# Busswitch_A.net
KiCad netlist of a schematic drawn in Altium Designer
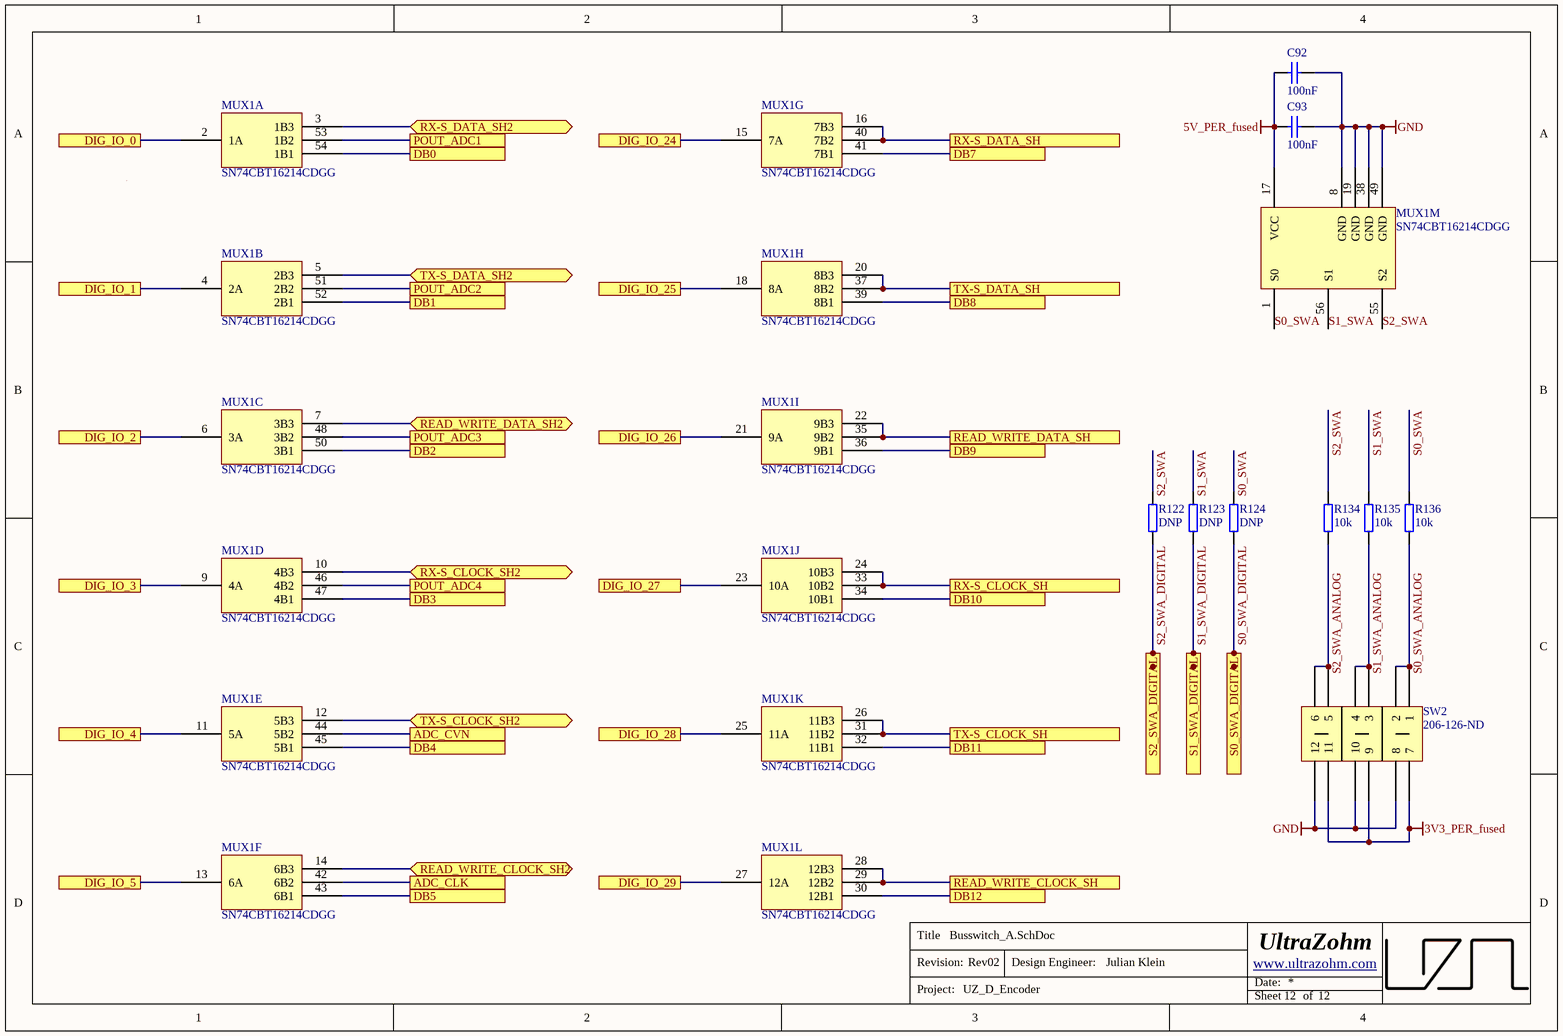
[diagram p0: Busswitch_A.SchDoc]

(export (version "E")
  (design (tool "Eeschema 10.0.6"))
  (components
    (comp (ref "C92")
      (value "100nF")
      (footprint "CAPC1608X07N")
      (fields (field (name "MF") "Würth") (field (name "MPN") "885012206071") (field (name "VOLTAGE") "25V"))
      (libsource (lib "UltraZohm_ADC") (part "Cap_0603"))
    )
    (comp (ref "C93")
      (value "100nF")
      (footprint "CAPC1608X07N")
      (fields (field (name "MF") "Würth") (field (name "MPN") "885012206071") (field (name "VOLTAGE") "25V"))
      (libsource (lib "UltraZohm_ADC") (part "Cap_0603"))
    )
    (comp (ref "MUX1")
      (value "SN74CBT16214CDGG")
      (footprint "TSSOP50P810X120-56N")
      (description "Multiplexer/Demultiplexer Bus Switch 1-Element CMOS 36-IN 56-Pin TSSOP Tube")
      (fields
        (field (name "MANUFACTURER") "Texas Instruments")
        (field (name "SUPPLIER PART NUMBER 1") "SN74CBT16214CDGG")
      )
      (libsource (lib "uz_d_encoder_lib") (part "SN74CBT16214CDGG"))
    )
    (comp (ref "R122")
      (value "DNP")
      (footprint "RESC1608X06N")
      (fields (field (name "MF") "Vishay") (field (name "MPN") "CRCW06030000Z0EAC"))
      (libsource (lib "UltraZohm_ADC") (part "R_0603"))
    )
    (comp (ref "R123")
      (value "DNP")
      (footprint "RESC1608X06N")
      (fields (field (name "MF") "Vishay") (field (name "MPN") "CRCW06030000Z0EAC"))
      (libsource (lib "UltraZohm_ADC") (part "R_0603"))
    )
    (comp (ref "R124")
      (value "DNP")
      (footprint "RESC1608X06N")
      (fields (field (name "MF") "Vishay") (field (name "MPN") "CRCW06030000Z0EAC"))
      (libsource (lib "UltraZohm_ADC") (part "R_0603"))
    )
    (comp (ref "R134")
      (value "10k")
      (footprint "RESC1608X06N")
      (fields (field (name "MF") "Vishay") (field (name "MPN") "CRCW06030000Z0EAC"))
      (libsource (lib "UltraZohm_ADC") (part "R_0603"))
    )
    (comp (ref "R135")
      (value "10k")
      (footprint "RESC1608X06N")
      (fields (field (name "MF") "Vishay") (field (name "MPN") "CRCW06030000Z0EAC"))
      (libsource (lib "UltraZohm_ADC") (part "R_0603"))
    )
    (comp (ref "R136")
      (value "10k")
      (footprint "RESC1608X06N")
      (fields (field (name "MF") "Vishay") (field (name "MPN") "CRCW06030000Z0EAC"))
      (libsource (lib "UltraZohm_ADC") (part "R_0603"))
    )
    (comp (ref "SW2")
      (value "206-126")
      (footprint "206-123")
      (description "Switch DIP OFF ON SPDT 6 Raised Slide 0.05A 24VDC PC Pins 2.54mm Thru-Hole Tube")
      (fields (field (name "MANUFACTURER") "CTS") (field (name "SUPPLIER PART NUMBER 1") "206-126-ND"))
      (libsource (lib "uz_d_encoder_lib") (part "206-126"))
    )
  )
  (nets
    (net (code "1") (name "/ADC_CLK") (class "Default")
      (node (ref "MUX1") (pin "42") (pinfunction "6B2_42") (pintype "passive"))
    )
    (net (code "2") (name "/ADC_CVN") (class "Default")
      (node (ref "MUX1") (pin "44") (pinfunction "5B2_44") (pintype "passive"))
    )
    (net (code "3") (name "/DB0") (class "Default")
      (node (ref "MUX1") (pin "54") (pinfunction "1B1_54") (pintype "passive"))
    )
    (net (code "4") (name "/DB1") (class "Default")
      (node (ref "MUX1") (pin "52") (pinfunction "2B1_52") (pintype "passive"))
    )
    (net (code "5") (name "/DB2") (class "Default")
      (node (ref "MUX1") (pin "50") (pinfunction "3B1_50") (pintype "passive"))
    )
    (net (code "6") (name "/DB3") (class "Default")
      (node (ref "MUX1") (pin "47") (pinfunction "4B1_47") (pintype "passive"))
    )
    (net (code "7") (name "/DB4") (class "Default")
      (node (ref "MUX1") (pin "45") (pinfunction "5B1_45") (pintype "passive"))
    )
    (net (code "8") (name "/DB5") (class "Default")
      (node (ref "MUX1") (pin "43") (pinfunction "6B1_43") (pintype "passive"))
    )
    (net (code "9") (name "/DB7") (class "Default")
      (node (ref "MUX1") (pin "41") (pinfunction "7B1_41") (pintype "passive"))
    )
    (net (code "10") (name "/DB8") (class "Default")
      (node (ref "MUX1") (pin "39") (pinfunction "8B1_39") (pintype "passive"))
    )
    (net (code "11") (name "/DB9") (class "Default")
      (node (ref "MUX1") (pin "36") (pinfunction "9B1_36") (pintype "passive"))
    )
    (net (code "12") (name "/DB10") (class "Default")
      (node (ref "MUX1") (pin "34") (pinfunction "10B1_34") (pintype "passive"))
    )
    (net (code "13") (name "/DB11") (class "Default")
      (node (ref "MUX1") (pin "32") (pinfunction "11B1_32") (pintype "passive"))
    )
    (net (code "14") (name "/DB12") (class "Default")
      (node (ref "MUX1") (pin "30") (pinfunction "12B1_30") (pintype "passive"))
    )
    (net (code "15") (name "/DIG_IO_0") (class "Default")
      (node (ref "MUX1") (pin "2") (pinfunction "1A_2") (pintype "passive"))
    )
    (net (code "16") (name "/DIG_IO_1") (class "Default")
      (node (ref "MUX1") (pin "4") (pinfunction "2A_4") (pintype "passive"))
    )
    (net (code "17") (name "/DIG_IO_2") (class "Default")
      (node (ref "MUX1") (pin "6") (pinfunction "3A_6") (pintype "passive"))
    )
    (net (code "18") (name "/DIG_IO_3") (class "Default")
      (node (ref "MUX1") (pin "9") (pinfunction "4A_9") (pintype "passive"))
    )
    (net (code "19") (name "/DIG_IO_4") (class "Default")
      (node (ref "MUX1") (pin "11") (pinfunction "5A_11") (pintype "passive"))
    )
    (net (code "20") (name "/DIG_IO_5") (class "Default")
      (node (ref "MUX1") (pin "13") (pinfunction "6A_13") (pintype "passive"))
    )
    (net (code "21") (name "/DIG_IO_24") (class "Default")
      (node (ref "MUX1") (pin "15") (pinfunction "7A_15") (pintype "passive"))
    )
    (net (code "22") (name "/DIG_IO_25") (class "Default")
      (node (ref "MUX1") (pin "18") (pinfunction "8A_18") (pintype "passive"))
    )
    (net (code "23") (name "/DIG_IO_26") (class "Default")
      (node (ref "MUX1") (pin "21") (pinfunction "9A_21") (pintype "passive"))
    )
    (net (code "24") (name "/DIG_IO_27") (class "Default")
      (node (ref "MUX1") (pin "23") (pinfunction "10A_23") (pintype "passive"))
    )
    (net (code "25") (name "/DIG_IO_28") (class "Default")
      (node (ref "MUX1") (pin "25") (pinfunction "11A_25") (pintype "passive"))
    )
    (net (code "26") (name "/DIG_IO_29") (class "Default")
      (node (ref "MUX1") (pin "27") (pinfunction "12A_27") (pintype "passive"))
    )
    (net (code "27") (name "/POUT_ADC1") (class "Default")
      (node (ref "MUX1") (pin "53") (pinfunction "1B2_53") (pintype "passive"))
    )
    (net (code "28") (name "/POUT_ADC2") (class "Default")
      (node (ref "MUX1") (pin "51") (pinfunction "2B2_51") (pintype "passive"))
    )
    (net (code "29") (name "/POUT_ADC3") (class "Default")
      (node (ref "MUX1") (pin "48") (pinfunction "3B2_48") (pintype "passive"))
    )
    (net (code "30") (name "/POUT_ADC4") (class "Default")
      (node (ref "MUX1") (pin "46") (pinfunction "4B2_46") (pintype "passive"))
    )
    (net (code "31") (name "/READ_WRITE_CLOCK_SH") (class "Default")
      (node (ref "MUX1") (pin "28") (pinfunction "12B3_28") (pintype "passive"))
      (node (ref "MUX1") (pin "29") (pinfunction "12B2_29") (pintype "passive"))
    )
    (net (code "32") (name "/READ_WRITE_CLOCK_SH2") (class "Default")
      (node (ref "MUX1") (pin "14") (pinfunction "6B3_14") (pintype "passive"))
    )
    (net (code "33") (name "/READ_WRITE_DATA_SH") (class "Default")
      (node (ref "MUX1") (pin "22") (pinfunction "9B3_22") (pintype "passive"))
      (node (ref "MUX1") (pin "35") (pinfunction "9B2_35") (pintype "passive"))
    )
    (net (code "34") (name "/READ_WRITE_DATA_SH2") (class "Default")
      (node (ref "MUX1") (pin "7") (pinfunction "3B3_7") (pintype "passive"))
    )
    (net (code "35") (name "/RX-S_CLOCK_SH") (class "Default")
      (node (ref "MUX1") (pin "24") (pinfunction "10B3_24") (pintype "passive"))
      (node (ref "MUX1") (pin "33") (pinfunction "10B2_33") (pintype "passive"))
    )
    (net (code "36") (name "/RX-S_CLOCK_SH2") (class "Default")
      (node (ref "MUX1") (pin "10") (pinfunction "4B3_10") (pintype "passive"))
    )
    (net (code "37") (name "/RX-S_DATA_SH") (class "Default")
      (node (ref "MUX1") (pin "16") (pinfunction "7B3_16") (pintype "passive"))
      (node (ref "MUX1") (pin "40") (pinfunction "7B2_40") (pintype "passive"))
    )
    (net (code "38") (name "/RX-S_DATA_SH2") (class "Default")
      (node (ref "MUX1") (pin "3") (pinfunction "1B3_3") (pintype "passive"))
    )
    (net (code "39") (name "/S0_SWA") (class "Default")
      (node (ref "MUX1") (pin "1") (pinfunction "S0_1") (pintype "passive"))
      (node (ref "R124") (pin "2") (pintype "passive"))
      (node (ref "R136") (pin "2") (pintype "passive"))
    )
    (net (code "40") (name "/S0_SWA_ANALOG") (class "Default")
      (node (ref "R136") (pin "1") (pintype "passive"))
      (node (ref "SW2") (pin "1") (pinfunction "1_1") (pintype "passive"))
      (node (ref "SW2") (pin "2") (pinfunction "2_2") (pintype "passive"))
    )
    (net (code "41") (name "/S0_SWA_DIGITAL") (class "Default")
      (node (ref "R124") (pin "1") (pintype "passive"))
    )
    (net (code "42") (name "/S1_SWA") (class "Default")
      (node (ref "MUX1") (pin "56") (pinfunction "S1_56") (pintype "passive"))
      (node (ref "R123") (pin "2") (pintype "passive"))
      (node (ref "R135") (pin "2") (pintype "passive"))
    )
    (net (code "43") (name "/S1_SWA_ANALOG") (class "Default")
      (node (ref "R135") (pin "1") (pintype "passive"))
      (node (ref "SW2") (pin "3") (pinfunction "3_3") (pintype "passive"))
      (node (ref "SW2") (pin "4") (pinfunction "4_4") (pintype "passive"))
    )
    (net (code "44") (name "/S1_SWA_DIGITAL") (class "Default")
      (node (ref "R123") (pin "1") (pintype "passive"))
    )
    (net (code "45") (name "/S2_SWA") (class "Default")
      (node (ref "MUX1") (pin "55") (pinfunction "S2_55") (pintype "passive"))
      (node (ref "R122") (pin "2") (pintype "passive"))
      (node (ref "R134") (pin "2") (pintype "passive"))
    )
    (net (code "46") (name "/S2_SWA_ANALOG") (class "Default")
      (node (ref "R134") (pin "1") (pintype "passive"))
      (node (ref "SW2") (pin "5") (pinfunction "5_5") (pintype "passive"))
      (node (ref "SW2") (pin "6") (pinfunction "6_6") (pintype "passive"))
    )
    (net (code "47") (name "/S2_SWA_DIGITAL") (class "Default")
      (node (ref "R122") (pin "1") (pintype "passive"))
    )
    (net (code "48") (name "/TX-S_CLOCK_SH") (class "Default")
      (node (ref "MUX1") (pin "26") (pinfunction "11B3_26") (pintype "passive"))
      (node (ref "MUX1") (pin "31") (pinfunction "11B2_31") (pintype "passive"))
    )
    (net (code "49") (name "/TX-S_CLOCK_SH2") (class "Default")
      (node (ref "MUX1") (pin "12") (pinfunction "5B3_12") (pintype "passive"))
    )
    (net (code "50") (name "/TX-S_DATA_SH") (class "Default")
      (node (ref "MUX1") (pin "20") (pinfunction "8B3_20") (pintype "passive"))
      (node (ref "MUX1") (pin "37") (pinfunction "8B2_37") (pintype "passive"))
    )
    (net (code "51") (name "/TX-S_DATA_SH2") (class "Default")
      (node (ref "MUX1") (pin "5") (pinfunction "2B3_5") (pintype "passive"))
    )
    (net (code "52") (name "3V3_PER_fused") (class "Default")
      (node (ref "SW2") (pin "11") (pinfunction "11_11") (pintype "passive"))
      (node (ref "SW2") (pin "7") (pinfunction "7_7") (pintype "passive"))
      (node (ref "SW2") (pin "9") (pinfunction "9_9") (pintype "passive"))
    )
    (net (code "53") (name "5V_PER_fused") (class "Default")
      (node (ref "C92") (pin "1") (pinfunction "1_1") (pintype "passive"))
      (node (ref "C93") (pin "1") (pinfunction "1_1") (pintype "passive"))
      (node (ref "MUX1") (pin "17") (pinfunction "VCC_17") (pintype "passive"))
    )
    (net (code "54") (name "GND") (class "Default")
      (node (ref "C92") (pin "2") (pinfunction "2_2") (pintype "passive"))
      (node (ref "C93") (pin "2") (pinfunction "2_2") (pintype "passive"))
      (node (ref "MUX1") (pin "19") (pinfunction "GND_19") (pintype "passive"))
      (node (ref "MUX1") (pin "38") (pinfunction "GND_38") (pintype "passive"))
      (node (ref "MUX1") (pin "49") (pinfunction "GND_49") (pintype "passive"))
      (node (ref "MUX1") (pin "8") (pinfunction "GND_8") (pintype "passive"))
      (node (ref "SW2") (pin "10") (pinfunction "10_10") (pintype "passive"))
      (node (ref "SW2") (pin "12") (pinfunction "12_12") (pintype "passive"))
      (node (ref "SW2") (pin "8") (pinfunction "8_8") (pintype "passive"))
    )
  )
)
